# ForEK1.net
KiCad netlist of a schematic drawn in Altium Designer
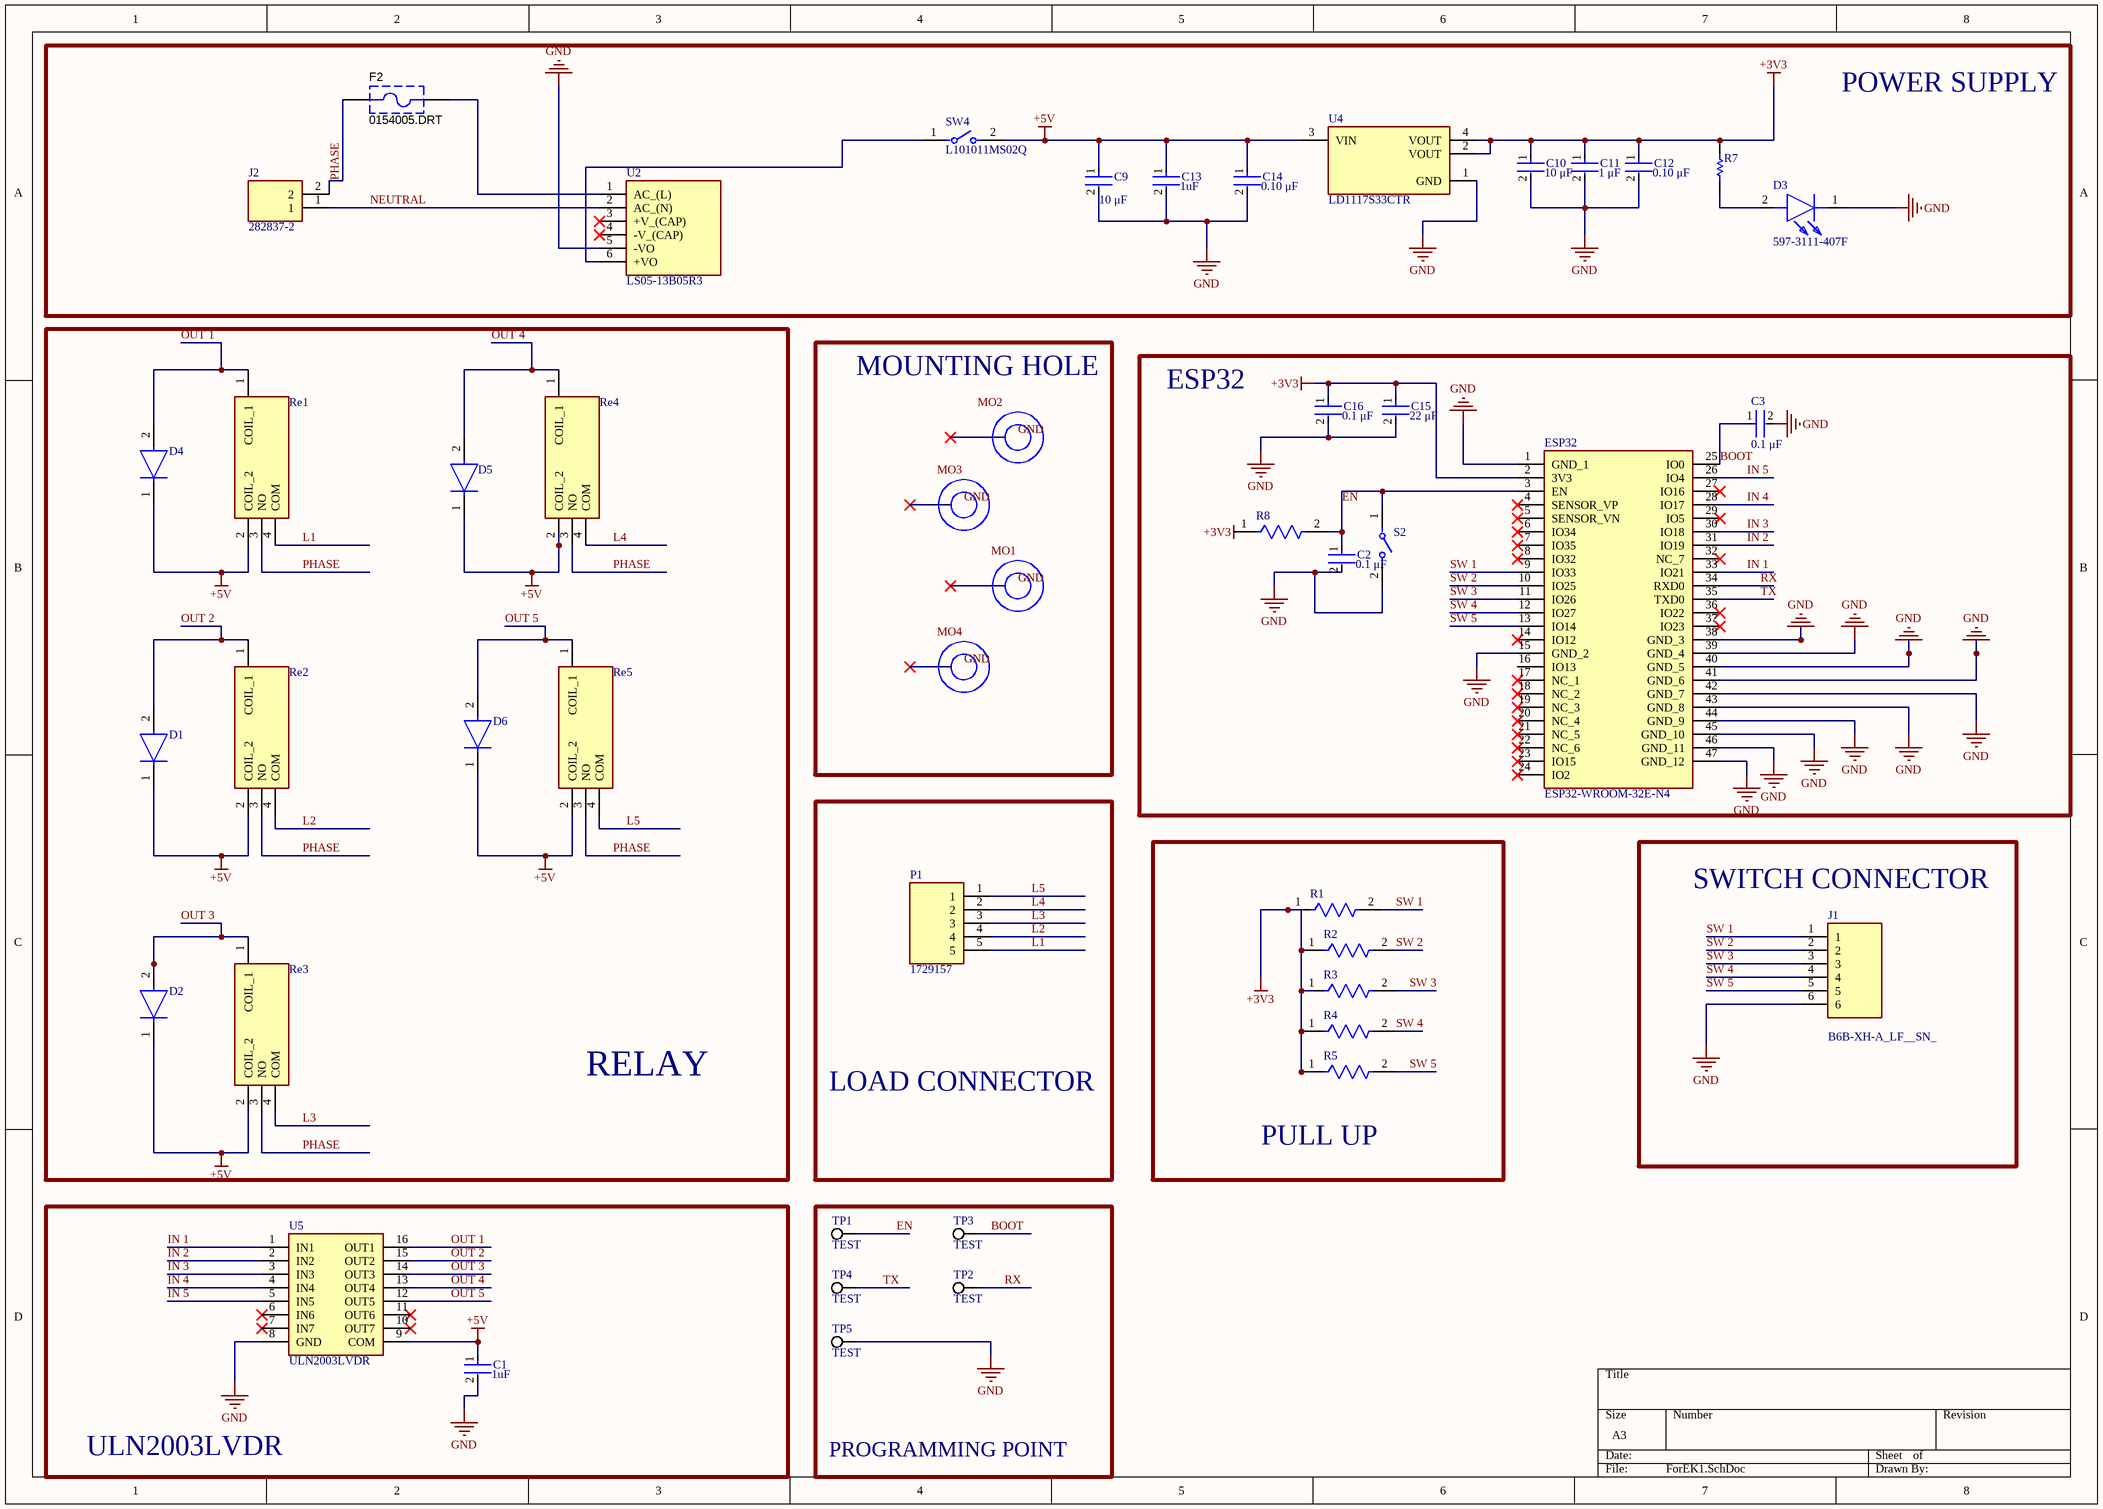
[diagram p0: ForEK1.SchDoc]

(export (version "E")
  (design (tool "Eeschema 10.0.6"))
  (components
    (comp (ref "C1")
      (value "C0402C104K8PACTU")
      (footprint "FP-C0402-BB-MFG")
      (description "CAP CER 0.1UF 10V X5R 0402")
      (fields
        (field (name "CAPACITANCE") "1uF")
        (field (name "MANUFACTURER") "Kemet")
        (field (name "TOLERANCE") "0.1")
      )
      (libsource (lib "Altium Content Vault") (part "b4654b650e69147ec39a6b967a45e02"))
    )
    (comp (ref "C2")
      (value "0.1 μF")
      (footprint "FP-C0402-BB-MFG")
      (description "CAP CER 0.1UF 10V X5R 0402")
      (fields (field (name "MANUFACTURER") "Kemet") (field (name "TOLERANCE") "0.1"))
      (libsource (lib "Altium Content Vault") (part "b4654b650e69147ec39a6b967a45e02"))
    )
    (comp (ref "C3")
      (value "0.1 μF")
      (footprint "FP-C0402-BB-MFG")
      (description "CAP CER 0.1UF 10V X5R 0402")
      (fields (field (name "MANUFACTURER") "Kemet") (field (name "TOLERANCE") "0.1"))
      (libsource (lib "Altium Content Vault") (part "b4654b650e69147ec39a6b967a45e02"))
    )
    (comp (ref "C9")
      (value "10 μF")
      (footprint "FP-C0402-BB-MFG")
      (description "CAP CER 0.1UF 10V X5R 0402")
      (fields (field (name "MANUFACTURER") "Kemet") (field (name "TOLERANCE") "0.1"))
      (libsource (lib "Altium Content Vault") (part "b4654b650e69147ec39a6b967a45e02"))
    )
    (comp (ref "C10")
      (value "10 μF")
      (footprint "FP-C0402-BB-MFG")
      (description "CAP CER 0.1UF 10V X5R 0402")
      (fields (field (name "MANUFACTURER") "Kemet") (field (name "TOLERANCE") "0.1"))
      (libsource (lib "Altium Content Vault") (part "b4654b650e69147ec39a6b967a45e02"))
    )
    (comp (ref "C11")
      (value "1 μF")
      (footprint "FP-C0402-BB-MFG")
      (description "CAP CER 0.1UF 10V X5R 0402")
      (fields (field (name "MANUFACTURER") "Kemet") (field (name "TOLERANCE") "0.1"))
      (libsource (lib "Altium Content Vault") (part "b4654b650e69147ec39a6b967a45e02"))
    )
    (comp (ref "C12")
      (value "C0402C104K8PACTU")
      (footprint "FP-C0402-BB-MFG")
      (description "CAP CER 0.1UF 10V X5R 0402")
      (fields
        (field (name "CAPACITANCE") "0.10 μF")
        (field (name "MANUFACTURER") "Kemet")
        (field (name "TOLERANCE") "0.1")
      )
      (libsource (lib "Altium Content Vault") (part "b4654b650e69147ec39a6b967a45e02"))
    )
    (comp (ref "C13")
      (value "C0402C104K8PACTU")
      (footprint "FP-C0402-BB-MFG")
      (description "CAP CER 0.1UF 10V X5R 0402")
      (fields
        (field (name "CAPACITANCE") "1uF")
        (field (name "MANUFACTURER") "Kemet")
        (field (name "TOLERANCE") "0.1")
      )
      (libsource (lib "Altium Content Vault") (part "b4654b650e69147ec39a6b967a45e02"))
    )
    (comp (ref "C14")
      (value "0.10 μF")
      (footprint "FP-C0402-BB-MFG")
      (description "CAP CER 0.1UF 10V X5R 0402")
      (fields (field (name "MANUFACTURER") "Kemet") (field (name "TOLERANCE") "0.1"))
      (libsource (lib "Altium Content Vault") (part "b4654b650e69147ec39a6b967a45e02"))
    )
    (comp (ref "C15")
      (value "22 μF")
      (footprint "FP-C0402-BB-MFG")
      (description "CAP CER 0.1UF 10V X5R 0402")
      (fields (field (name "MANUFACTURER") "Kemet") (field (name "TOLERANCE") "0.1"))
      (libsource (lib "Altium Content Vault") (part "b4654b650e69147ec39a6b967a45e02"))
    )
    (comp (ref "C16")
      (value "0.1 μF")
      (footprint "FP-C0402-BB-MFG")
      (description "CAP CER 0.1UF 10V X5R 0402")
      (fields (field (name "MANUFACTURER") "Kemet") (field (name "TOLERANCE") "0.1"))
      (libsource (lib "Altium Content Vault") (part "b4654b650e69147ec39a6b967a45e02"))
    )
    (comp (ref "D1")
      (value "1N4148")
      (footprint "FP-017AG-MFG")
      (description "DIODE GEN PURP 100V 200MA DO35")
      (fields (field (name "VOLTAGE") "100V"))
      (libsource (lib "Altium Content Vault") (part "d7152d700b627762746794eb795d46e"))
    )
    (comp (ref "D2")
      (value "1N4148")
      (footprint "FP-017AG-MFG")
      (description "DIODE GEN PURP 100V 200MA DO35")
      (fields (field (name "VOLTAGE") "100V"))
      (libsource (lib "Altium Content Vault") (part "d7152d700b627762746794eb795d46e"))
    )
    (comp (ref "D3")
      (value "597-3111-407F")
      (footprint "SamacSys:LEDC3015X150N")
      (description "LED")
      (fields (field (name "MOUSER PART NUMBER") "645-597-3111-407F"))
      (libsource (lib "*") (part "597-3111-407F"))
    )
    (comp (ref "D4")
      (value "1N4148")
      (footprint "FP-017AG-MFG")
      (description "DIODE GEN PURP 100V 200MA DO35")
      (fields (field (name "VOLTAGE") "100V"))
      (libsource (lib "Altium Content Vault") (part "d7152d700b627762746794eb795d46e"))
    )
    (comp (ref "D5")
      (value "1N4148")
      (footprint "FP-017AG-MFG")
      (description "DIODE GEN PURP 100V 200MA DO35")
      (fields (field (name "VOLTAGE") "100V"))
      (libsource (lib "Altium Content Vault") (part "d7152d700b627762746794eb795d46e"))
    )
    (comp (ref "D6")
      (value "1N4148")
      (footprint "FP-017AG-MFG")
      (description "DIODE GEN PURP 100V 200MA DO35")
      (fields (field (name "VOLTAGE") "100V"))
      (libsource (lib "Altium Content Vault") (part "d7152d700b627762746794eb795d46e"))
    )
    (comp (ref "ESP32")
      (value "ESP32-WROOM-32E-N4")
      (footprint "SamacSys:ESP32WROOM32EN4")
      (description "Integrated Circuit")
      (fields (field (name "MOUSER PART NUMBER") "356-ESP32WRM32E132PH"))
      (libsource (lib "*") (part "ESP32-WROOM-32E-N4"))
    )
    (comp (ref "F2")
      (value "0154005.DRT")
      (footprint "LFUS-154_V")
      (description "Fuse and Holder Combination, 125 V, 5 A, -55 to 125 degC, 2-Pin SMD, RoHS, Tape and Reel")
      (fields (field (name "MANUFACTURER") "Littelfuse"))
      (libsource (lib "Altium Content Vault") (part "FUSE_HOLDER-2"))
    )
    (comp (ref "J1")
      (value "B6B-XH-A_LF__SN_")
      (footprint "SamacSys:SHDR6W64P0X250_1X6_1740X575X700P")
      (description "Connector")
      (fields
        (field (name "MANUFACTURER_PART_NUMBER") "B6B-XH-A(LF)(SN)")
        (field (name "MOUSER PART NUMBER") "306-B6BXHALFSN")
      )
      (libsource (lib "*") (part "B6B-XH-A_LF__SN_"))
    )
    (comp (ref "J2")
      (value "282837-2")
      (footprint "SamacSys:2828372")
      (description "Connector")
      (fields (field (name "MOUSER PART NUMBER") "571-2828372"))
      (libsource (lib "*") (part "282837-2"))
    )
    (comp (ref "P1")
      (value "1729157")
      (footprint "SamacSys:1729157")
      (description "Connector")
      (fields (field (name "MOUSER PART NUMBER") "651-1729157"))
      (libsource (lib "*") (part "1729157"))
    )
    (comp (ref "R1")
      (value "CRCW040210K0JNED")
      (footprint "FP-CRCW0402-e3-IPC_B")
      (description "RES Thick Film, 10kΩ, 5%, 0.063W, 200ppm/°C, 0402")
      (fields (field (name "TOLERANCE") "5%"))
      (libsource (lib "Altium Content Vault") (part "1029c3af85768c4190bb7ad29bc67b5"))
    )
    (comp (ref "R2")
      (value "CRCW040210K0JNED")
      (footprint "FP-CRCW0402-e3-IPC_B")
      (description "RES Thick Film, 10kΩ, 5%, 0.063W, 200ppm/°C, 0402")
      (fields (field (name "TOLERANCE") "5%"))
      (libsource (lib "Altium Content Vault") (part "1029c3af85768c4190bb7ad29bc67b5"))
    )
    (comp (ref "R3")
      (value "CRCW040210K0JNED")
      (footprint "FP-CRCW0402-e3-IPC_B")
      (description "RES Thick Film, 10kΩ, 5%, 0.063W, 200ppm/°C, 0402")
      (fields (field (name "TOLERANCE") "5%"))
      (libsource (lib "Altium Content Vault") (part "1029c3af85768c4190bb7ad29bc67b5"))
    )
    (comp (ref "R4")
      (value "CRCW040210K0JNED")
      (footprint "FP-CRCW0402-e3-IPC_B")
      (description "RES Thick Film, 10kΩ, 5%, 0.063W, 200ppm/°C, 0402")
      (fields (field (name "TOLERANCE") "5%"))
      (libsource (lib "Altium Content Vault") (part "1029c3af85768c4190bb7ad29bc67b5"))
    )
    (comp (ref "R5")
      (value "CRCW040210K0JNED")
      (footprint "FP-CRCW0402-e3-IPC_B")
      (description "RES Thick Film, 10kΩ, 5%, 0.063W, 200ppm/°C, 0402")
      (fields (field (name "TOLERANCE") "5%"))
      (libsource (lib "Altium Content Vault") (part "1029c3af85768c4190bb7ad29bc67b5"))
    )
    (comp (ref "R7")
      (value "ERJ-3EKF3300V")
      (footprint "RESC1608X55X30LL15T15")
      (description "Chip Resistor, 330 Ohm, +/- 1%, 0.1 W, -55 to 155 degC, 0603 (1608 Metric), RoHS, Tape and Reel")
      (libsource (lib "Altium Content Vault") (part "RES-2"))
    )
    (comp (ref "R8")
      (value "CRCW040210K0JNED")
      (footprint "FP-CRCW0402-e3-IPC_B")
      (description "RES Thick Film, 10kΩ, 5%, 0.063W, 200ppm/°C, 0402")
      (fields (field (name "TOLERANCE") "5%"))
      (libsource (lib "Altium Content Vault") (part "1029c3af85768c4190bb7ad29bc67b5"))
    )
    (comp (ref "Re1")
      (value "HF46F-G_5-HS1T")
      (footprint "SamacSys:HF46FG5HS1T")
      (description "Relay or Contactor")
      (fields (field (name "MANUFACTURER_PART_NUMBER") "HF46F-G/5-HS1T"))
      (libsource (lib "*") (part "HF46F-G_5-HS1T"))
    )
    (comp (ref "Re2")
      (value "HF46F-G_5-HS1T")
      (footprint "SamacSys:HF46FG5HS1T")
      (description "Relay or Contactor")
      (fields (field (name "MANUFACTURER_PART_NUMBER") "HF46F-G/5-HS1T"))
      (libsource (lib "*") (part "HF46F-G_5-HS1T"))
    )
    (comp (ref "Re3")
      (value "HF46F-G_5-HS1T")
      (footprint "SamacSys:HF46FG5HS1T")
      (description "Relay or Contactor")
      (fields (field (name "MANUFACTURER_PART_NUMBER") "HF46F-G/5-HS1T"))
      (libsource (lib "*") (part "HF46F-G_5-HS1T"))
    )
    (comp (ref "Re4")
      (value "HF46F-G_5-HS1T")
      (footprint "SamacSys:HF46FG5HS1T")
      (description "Relay or Contactor")
      (fields (field (name "MANUFACTURER_PART_NUMBER") "HF46F-G/5-HS1T"))
      (libsource (lib "*") (part "HF46F-G_5-HS1T"))
    )
    (comp (ref "Re5")
      (value "HF46F-G_5-HS1T")
      (footprint "SamacSys:HF46FG5HS1T")
      (description "Relay or Contactor")
      (fields (field (name "MANUFACTURER_PART_NUMBER") "HF46F-G/5-HS1T"))
      (libsource (lib "*") (part "HF46F-G_5-HS1T"))
    )
    (comp (ref "S2")
      (value "L101011MS02Q")
      (footprint "FP-L101011MS02Q-MFG")
      (description "SWITCH SLIDE SPST 4A 125V")
      (libsource (lib "Altium Content Vault") (part "bb27bde45df87f1f469753f287ef5ae"))
    )
    (comp (ref "SW4")
      (value "L101011MS02Q")
      (footprint "FP-L101011MS02Q-MFG")
      (description "SWITCH SLIDE SPST 4A 125V")
      (libsource (lib "Altium Content Vault") (part "bb27bde45df87f1f469753f287ef5ae"))
    )
    (comp (ref "TP1")
      (value "TEST")
      (footprint "KSTN-5012_V")
      (description "Test Point, White, Through Hole, RoHS, Bulk")
      (fields (field (name "MANUFACTURER") "Keystone"))
      (libsource (lib "Altium Content Vault") (part "TESTPOINT_WHITE"))
    )
    (comp (ref "TP2")
      (value "TEST")
      (footprint "KSTN-5012_V")
      (description "Test Point, White, Through Hole, RoHS, Bulk")
      (fields (field (name "MANUFACTURER") "Keystone"))
      (libsource (lib "Altium Content Vault") (part "TESTPOINT_WHITE"))
    )
    (comp (ref "TP3")
      (value "TEST")
      (footprint "KSTN-5012_V")
      (description "Test Point, White, Through Hole, RoHS, Bulk")
      (fields (field (name "MANUFACTURER") "Keystone"))
      (libsource (lib "Altium Content Vault") (part "TESTPOINT_WHITE"))
    )
    (comp (ref "TP4")
      (value "TEST")
      (footprint "KSTN-5012_V")
      (description "Test Point, White, Through Hole, RoHS, Bulk")
      (fields (field (name "MANUFACTURER") "Keystone"))
      (libsource (lib "Altium Content Vault") (part "TESTPOINT_WHITE"))
    )
    (comp (ref "TP5")
      (value "TEST")
      (footprint "KSTN-5012_V")
      (description "Test Point, White, Through Hole, RoHS, Bulk")
      (fields (field (name "MANUFACTURER") "Keystone"))
      (libsource (lib "Altium Content Vault") (part "TESTPOINT_WHITE"))
    )
    (comp (ref "U2")
      (value "LS05-13B05R3")
      (footprint "SamacSys:LS0513B05R3")
      (description "Power Supply")
      (libsource (lib "*") (part "LS05-13B05R3"))
    )
    (comp (ref "U4")
      (value "LD1117S33CTR")
      (footprint "FP-SOT-223-0046067_14-MFG")
      (description "IC REG LINEAR 3.3V 800MA SOT223")
      (libsource (lib "Altium Content Vault") (part "7818869c5c16ceab15634627166a29d"))
    )
    (comp (ref "U5")
      (value "ULN2003LVDR")
      (footprint "SamacSys:SOIC127P600X175-16N")
      (description "Integrated Circuit")
      (fields (field (name "MOUSER PART NUMBER") "595-ULN2003LVDR"))
      (libsource (lib "*") (part "ULN2003LVDR"))
    )
  )
  (nets
    (net (code "1") (name "+3V3") (class "Default")
      (node (ref "C10") (pin "1") (pinfunction "1_1") (pintype "passive"))
      (node (ref "C11") (pin "1") (pinfunction "1_1") (pintype "passive"))
      (node (ref "C12") (pin "1") (pinfunction "1_1") (pintype "passive"))
      (node (ref "C15") (pin "1") (pinfunction "1_1") (pintype "passive"))
      (node (ref "C16") (pin "1") (pinfunction "1_1") (pintype "passive"))
      (node (ref "ESP32") (pin "2") (pinfunction "3V3_2") (pintype "passive"))
      (node (ref "R1") (pin "1") (pinfunction "1_1") (pintype "passive"))
      (node (ref "R2") (pin "1") (pinfunction "1_1") (pintype "passive"))
      (node (ref "R3") (pin "1") (pinfunction "1_1") (pintype "passive"))
      (node (ref "R4") (pin "1") (pinfunction "1_1") (pintype "passive"))
      (node (ref "R5") (pin "1") (pinfunction "1_1") (pintype "passive"))
      (node (ref "R7") (pin "2") (pinfunction "2_2") (pintype "passive"))
      (node (ref "U4") (pin "2") (pinfunction "VOUT_2") (pintype "power_in"))
      (node (ref "U4") (pin "4") (pinfunction "VOUT_4") (pintype "power_in"))
    )
    (net (code "2") (name "+5V") (class "Default")
      (node (ref "C1") (pin "1") (pinfunction "1_1") (pintype "passive"))
      (node (ref "C13") (pin "1") (pinfunction "1_1") (pintype "passive"))
      (node (ref "C14") (pin "1") (pinfunction "1_1") (pintype "passive"))
      (node (ref "C9") (pin "1") (pinfunction "1_1") (pintype "passive"))
      (node (ref "D1") (pin "1") (pinfunction "C_1") (pintype "passive"))
      (node (ref "D2") (pin "1") (pinfunction "C_1") (pintype "passive"))
      (node (ref "D4") (pin "1") (pinfunction "C_1") (pintype "passive"))
      (node (ref "D5") (pin "1") (pinfunction "C_1") (pintype "passive"))
      (node (ref "D6") (pin "1") (pinfunction "C_1") (pintype "passive"))
      (node (ref "Re1") (pin "2") (pinfunction "COIL_2_2") (pintype "passive"))
      (node (ref "Re2") (pin "2") (pinfunction "COIL_2_2") (pintype "passive"))
      (node (ref "Re3") (pin "2") (pinfunction "COIL_2_2") (pintype "passive"))
      (node (ref "Re4") (pin "2") (pinfunction "COIL_2_2") (pintype "passive"))
      (node (ref "Re5") (pin "2") (pinfunction "COIL_2_2") (pintype "passive"))
      (node (ref "SW4") (pin "2") (pinfunction "2_2") (pintype "passive"))
      (node (ref "U4") (pin "3") (pinfunction "VIN_3") (pintype "power_in"))
      (node (ref "U5") (pin "9") (pinfunction "COM_9") (pintype "passive"))
    )
    (net (code "3") (name "/BOOT") (class "Default")
      (node (ref "C3") (pin "1") (pinfunction "1_1") (pintype "passive"))
      (node (ref "ESP32") (pin "25") (pinfunction "IO0_25") (pintype "passive"))
      (node (ref "TP3") (pin "1") (pinfunction "1_1") (pintype "passive"))
    )
    (net (code "4") (name "/EN") (class "Default")
      (node (ref "C2") (pin "1") (pinfunction "1_1") (pintype "passive"))
      (node (ref "ESP32") (pin "3") (pinfunction "EN_3") (pintype "passive"))
      (node (ref "R8") (pin "2") (pinfunction "2_2") (pintype "passive"))
      (node (ref "S2") (pin "1") (pinfunction "1_1") (pintype "passive"))
      (node (ref "TP1") (pin "1") (pinfunction "1_1") (pintype "passive"))
    )
    (net (code "5") (name "/IN 1") (class "Default")
      (node (ref "ESP32") (pin "33") (pinfunction "IO21_33") (pintype "passive"))
      (node (ref "U5") (pin "1") (pinfunction "IN1_1") (pintype "passive"))
    )
    (net (code "6") (name "/IN 2") (class "Default")
      (node (ref "ESP32") (pin "31") (pinfunction "IO19_31") (pintype "passive"))
      (node (ref "U5") (pin "2") (pinfunction "IN2_2") (pintype "passive"))
    )
    (net (code "7") (name "/IN 3") (class "Default")
      (node (ref "ESP32") (pin "30") (pinfunction "IO18_30") (pintype "passive"))
      (node (ref "U5") (pin "3") (pinfunction "IN3_3") (pintype "passive"))
    )
    (net (code "8") (name "/IN 4") (class "Default")
      (node (ref "ESP32") (pin "28") (pinfunction "IO17_28") (pintype "passive"))
      (node (ref "U5") (pin "4") (pinfunction "IN4_4") (pintype "passive"))
    )
    (net (code "9") (name "/IN 5") (class "Default")
      (node (ref "ESP32") (pin "26") (pinfunction "IO4_26") (pintype "passive"))
      (node (ref "U5") (pin "5") (pinfunction "IN5_5") (pintype "passive"))
    )
    (net (code "10") (name "/L1") (class "Default")
      (node (ref "P1") (pin "5") (pinfunction "5_5") (pintype "passive"))
      (node (ref "Re1") (pin "4") (pinfunction "COM_4") (pintype "passive"))
    )
    (net (code "11") (name "/L2") (class "Default")
      (node (ref "P1") (pin "4") (pinfunction "4_4") (pintype "passive"))
      (node (ref "Re2") (pin "4") (pinfunction "COM_4") (pintype "passive"))
    )
    (net (code "12") (name "/L3") (class "Default")
      (node (ref "P1") (pin "3") (pinfunction "3_3") (pintype "passive"))
      (node (ref "Re3") (pin "4") (pinfunction "COM_4") (pintype "passive"))
    )
    (net (code "13") (name "/L4") (class "Default")
      (node (ref "P1") (pin "2") (pinfunction "2_2") (pintype "passive"))
      (node (ref "Re4") (pin "4") (pinfunction "COM_4") (pintype "passive"))
    )
    (net (code "14") (name "/L5") (class "Default")
      (node (ref "P1") (pin "1") (pinfunction "1_1") (pintype "passive"))
      (node (ref "Re5") (pin "4") (pinfunction "COM_4") (pintype "passive"))
    )
    (net (code "19") (name "/NEUTRAL") (class "Default")
      (node (ref "J2") (pin "1") (pinfunction "1_1") (pintype "passive"))
      (node (ref "U2") (pin "2") (pinfunction "AC_(N)_2") (pintype "passive"))
    )
    (net (code "20") (name "/OUT 1") (class "Default")
      (node (ref "D4") (pin "2") (pinfunction "A_2") (pintype "passive"))
      (node (ref "Re1") (pin "1") (pinfunction "COIL_1_1") (pintype "passive"))
      (node (ref "U5") (pin "16") (pinfunction "OUT1_16") (pintype "passive"))
    )
    (net (code "21") (name "/OUT 2") (class "Default")
      (node (ref "D1") (pin "2") (pinfunction "A_2") (pintype "passive"))
      (node (ref "Re2") (pin "1") (pinfunction "COIL_1_1") (pintype "passive"))
      (node (ref "U5") (pin "15") (pinfunction "OUT2_15") (pintype "passive"))
    )
    (net (code "22") (name "/OUT 3") (class "Default")
      (node (ref "D2") (pin "2") (pinfunction "A_2") (pintype "passive"))
      (node (ref "Re3") (pin "1") (pinfunction "COIL_1_1") (pintype "passive"))
      (node (ref "U5") (pin "14") (pinfunction "OUT3_14") (pintype "passive"))
    )
    (net (code "23") (name "/OUT 4") (class "Default")
      (node (ref "D5") (pin "2") (pinfunction "A_2") (pintype "passive"))
      (node (ref "Re4") (pin "1") (pinfunction "COIL_1_1") (pintype "passive"))
      (node (ref "U5") (pin "13") (pinfunction "OUT4_13") (pintype "passive"))
    )
    (net (code "24") (name "/OUT 5") (class "Default")
      (node (ref "D6") (pin "2") (pinfunction "A_2") (pintype "passive"))
      (node (ref "Re5") (pin "1") (pinfunction "COIL_1_1") (pintype "passive"))
      (node (ref "U5") (pin "12") (pinfunction "OUT5_12") (pintype "passive"))
    )
    (net (code "25") (name "/PHASE") (class "Default")
      (node (ref "F2") (pin "1") (pinfunction "1_1") (pintype "passive"))
      (node (ref "J2") (pin "2") (pinfunction "2_2") (pintype "passive"))
      (node (ref "Re1") (pin "3") (pinfunction "NO_3") (pintype "passive"))
      (node (ref "Re2") (pin "3") (pinfunction "NO_3") (pintype "passive"))
      (node (ref "Re3") (pin "3") (pinfunction "NO_3") (pintype "passive"))
      (node (ref "Re4") (pin "3") (pinfunction "NO_3") (pintype "passive"))
      (node (ref "Re5") (pin "3") (pinfunction "NO_3") (pintype "passive"))
    )
    (net (code "26") (name "/RX") (class "Default")
      (node (ref "ESP32") (pin "34") (pinfunction "RXD0_34") (pintype "passive"))
      (node (ref "TP2") (pin "1") (pinfunction "1_1") (pintype "passive"))
    )
    (net (code "27") (name "/SW 1") (class "Default")
      (node (ref "ESP32") (pin "9") (pinfunction "IO33_9") (pintype "passive"))
      (node (ref "J1") (pin "1") (pinfunction "1_1") (pintype "passive"))
      (node (ref "R1") (pin "2") (pinfunction "2_2") (pintype "passive"))
    )
    (net (code "28") (name "/SW 2") (class "Default")
      (node (ref "ESP32") (pin "10") (pinfunction "IO25_10") (pintype "passive"))
      (node (ref "J1") (pin "2") (pinfunction "2_2") (pintype "passive"))
      (node (ref "R2") (pin "2") (pinfunction "2_2") (pintype "passive"))
    )
    (net (code "29") (name "/SW 3") (class "Default")
      (node (ref "ESP32") (pin "11") (pinfunction "IO26_11") (pintype "passive"))
      (node (ref "J1") (pin "3") (pinfunction "3_3") (pintype "passive"))
      (node (ref "R3") (pin "2") (pinfunction "2_2") (pintype "passive"))
    )
    (net (code "30") (name "/SW 4") (class "Default")
      (node (ref "ESP32") (pin "12") (pinfunction "IO27_12") (pintype "passive"))
      (node (ref "J1") (pin "4") (pinfunction "4_4") (pintype "passive"))
      (node (ref "R4") (pin "2") (pinfunction "2_2") (pintype "passive"))
    )
    (net (code "31") (name "/SW 5") (class "Default")
      (node (ref "ESP32") (pin "13") (pinfunction "IO14_13") (pintype "passive"))
      (node (ref "J1") (pin "5") (pinfunction "5_5") (pintype "passive"))
      (node (ref "R5") (pin "2") (pinfunction "2_2") (pintype "passive"))
    )
    (net (code "32") (name "/TX") (class "Default")
      (node (ref "ESP32") (pin "35") (pinfunction "TXD0_35") (pintype "passive"))
      (node (ref "TP4") (pin "1") (pinfunction "1_1") (pintype "passive"))
    )
    (net (code "33") (name "GND") (class "Default")
      (node (ref "C1") (pin "2") (pinfunction "2_2") (pintype "passive"))
      (node (ref "C10") (pin "2") (pinfunction "2_2") (pintype "passive"))
      (node (ref "C11") (pin "2") (pinfunction "2_2") (pintype "passive"))
      (node (ref "C12") (pin "2") (pinfunction "2_2") (pintype "passive"))
      (node (ref "C13") (pin "2") (pinfunction "2_2") (pintype "passive"))
      (node (ref "C14") (pin "2") (pinfunction "2_2") (pintype "passive"))
      (node (ref "C15") (pin "2") (pinfunction "2_2") (pintype "passive"))
      (node (ref "C16") (pin "2") (pinfunction "2_2") (pintype "passive"))
      (node (ref "C2") (pin "2") (pinfunction "2_2") (pintype "passive"))
      (node (ref "C3") (pin "2") (pinfunction "2_2") (pintype "passive"))
      (node (ref "C9") (pin "2") (pinfunction "2_2") (pintype "passive"))
      (node (ref "D3") (pin "1") (pinfunction "K_1") (pintype "passive"))
      (node (ref "ESP32") (pin "1") (pinfunction "GND_1_1") (pintype "passive"))
      (node (ref "ESP32") (pin "15") (pinfunction "GND_2_15") (pintype "passive"))
      (node (ref "ESP32") (pin "38") (pinfunction "GND_3_38") (pintype "passive"))
      (node (ref "ESP32") (pin "39") (pinfunction "GND_4_39") (pintype "passive"))
      (node (ref "ESP32") (pin "40") (pinfunction "GND_5_40") (pintype "passive"))
      (node (ref "ESP32") (pin "41") (pinfunction "GND_6_41") (pintype "passive"))
      (node (ref "ESP32") (pin "42") (pinfunction "GND_7_42") (pintype "passive"))
      (node (ref "ESP32") (pin "43") (pinfunction "GND_8_43") (pintype "passive"))
      (node (ref "ESP32") (pin "44") (pinfunction "GND_9_44") (pintype "passive"))
      (node (ref "ESP32") (pin "45") (pinfunction "GND_10_45") (pintype "passive"))
      (node (ref "ESP32") (pin "46") (pinfunction "GND_11_46") (pintype "passive"))
      (node (ref "ESP32") (pin "47") (pinfunction "GND_12_47") (pintype "passive"))
      (node (ref "J1") (pin "6") (pinfunction "6_6") (pintype "passive"))
      (node (ref "S2") (pin "2") (pinfunction "2_2") (pintype "passive"))
      (node (ref "TP5") (pin "1") (pinfunction "1_1") (pintype "passive"))
      (node (ref "U2") (pin "5") (pinfunction "-VO_5") (pintype "passive"))
      (node (ref "U4") (pin "1") (pinfunction "GND_1") (pintype "power_in"))
      (node (ref "U5") (pin "8") (pinfunction "GND_8") (pintype "passive"))
    )
    (net (code "34") (name "Net-(D3-A)") (class "Default")
      (node (ref "D3") (pin "2") (pinfunction "A_2") (pintype "passive"))
      (node (ref "R7") (pin "1") (pinfunction "1_1") (pintype "passive"))
    )
    (net (code "35") (name "Net-(U2-+VO)") (class "Default")
      (node (ref "SW4") (pin "1") (pinfunction "1_1") (pintype "passive"))
      (node (ref "U2") (pin "6") (pinfunction "+VO_6") (pintype "passive"))
    )
    (net (code "36") (name "Net-(U2-AC_(L))") (class "Default")
      (node (ref "F2") (pin "2") (pinfunction "2_2") (pintype "passive"))
      (node (ref "U2") (pin "1") (pinfunction "AC_(L)_1") (pintype "passive"))
    )
    (net (code "37") (name "unconnected-(ESP32-IO2-Pad24)") (class "Default")
      (node (ref "ESP32") (pin "24") (pinfunction "IO2_24") (pintype "passive+no_connect"))
    )
    (net (code "38") (name "unconnected-(ESP32-IO5-Pad29)") (class "Default")
      (node (ref "ESP32") (pin "29") (pinfunction "IO5_29") (pintype "passive+no_connect"))
    )
    (net (code "39") (name "unconnected-(ESP32-IO12-Pad14)") (class "Default")
      (node (ref "ESP32") (pin "14") (pinfunction "IO12_14") (pintype "passive+no_connect"))
    )
    (net (code "40") (name "unconnected-(ESP32-IO13-Pad16)") (class "Default")
      (node (ref "ESP32") (pin "16") (pinfunction "IO13_16") (pintype "passive"))
    )
    (net (code "41") (name "unconnected-(ESP32-IO15-Pad23)") (class "Default")
      (node (ref "ESP32") (pin "23") (pinfunction "IO15_23") (pintype "passive+no_connect"))
    )
    (net (code "42") (name "unconnected-(ESP32-IO16-Pad27)") (class "Default")
      (node (ref "ESP32") (pin "27") (pinfunction "IO16_27") (pintype "passive+no_connect"))
    )
    (net (code "43") (name "unconnected-(ESP32-IO22-Pad36)") (class "Default")
      (node (ref "ESP32") (pin "36") (pinfunction "IO22_36") (pintype "passive+no_connect"))
    )
    (net (code "44") (name "unconnected-(ESP32-IO23-Pad37)") (class "Default")
      (node (ref "ESP32") (pin "37") (pinfunction "IO23_37") (pintype "passive+no_connect"))
    )
    (net (code "45") (name "unconnected-(ESP32-IO32-Pad8)") (class "Default")
      (node (ref "ESP32") (pin "8") (pinfunction "IO32_8") (pintype "passive+no_connect"))
    )
    (net (code "46") (name "unconnected-(ESP32-IO34-Pad6)") (class "Default")
      (node (ref "ESP32") (pin "6") (pinfunction "IO34_6") (pintype "passive+no_connect"))
    )
    (net (code "47") (name "unconnected-(ESP32-IO35-Pad7)") (class "Default")
      (node (ref "ESP32") (pin "7") (pinfunction "IO35_7") (pintype "passive+no_connect"))
    )
    (net (code "48") (name "unconnected-(ESP32-NC_1-Pad17)") (class "Default")
      (node (ref "ESP32") (pin "17") (pinfunction "NC_1_17") (pintype "passive+no_connect"))
    )
    (net (code "49") (name "unconnected-(ESP32-NC_2-Pad18)") (class "Default")
      (node (ref "ESP32") (pin "18") (pinfunction "NC_2_18") (pintype "passive+no_connect"))
    )
    (net (code "50") (name "unconnected-(ESP32-NC_3-Pad19)") (class "Default")
      (node (ref "ESP32") (pin "19") (pinfunction "NC_3_19") (pintype "passive+no_connect"))
    )
    (net (code "51") (name "unconnected-(ESP32-NC_4-Pad20)") (class "Default")
      (node (ref "ESP32") (pin "20") (pinfunction "NC_4_20") (pintype "passive+no_connect"))
    )
    (net (code "52") (name "unconnected-(ESP32-NC_5-Pad21)") (class "Default")
      (node (ref "ESP32") (pin "21") (pinfunction "NC_5_21") (pintype "passive+no_connect"))
    )
    (net (code "53") (name "unconnected-(ESP32-NC_6-Pad22)") (class "Default")
      (node (ref "ESP32") (pin "22") (pinfunction "NC_6_22") (pintype "passive+no_connect"))
    )
    (net (code "54") (name "unconnected-(ESP32-NC_7-Pad32)") (class "Default")
      (node (ref "ESP32") (pin "32") (pinfunction "NC_7_32") (pintype "passive+no_connect"))
    )
    (net (code "55") (name "unconnected-(ESP32-SENSOR_VN-Pad5)") (class "Default")
      (node (ref "ESP32") (pin "5") (pinfunction "SENSOR_VN_5") (pintype "passive+no_connect"))
    )
    (net (code "56") (name "unconnected-(ESP32-SENSOR_VP-Pad4)") (class "Default")
      (node (ref "ESP32") (pin "4") (pinfunction "SENSOR_VP_4") (pintype "passive+no_connect"))
    )
    (net (code "57") (name "unconnected-(R8-Pad1)") (class "Default")
      (node (ref "R8") (pin "1") (pinfunction "1_1") (pintype "passive"))
    )
    (net (code "58") (name "unconnected-(U2-+V_(CAP)-Pad3)") (class "Default")
      (node (ref "U2") (pin "3") (pinfunction "+V_(CAP)_3") (pintype "passive+no_connect"))
    )
    (net (code "59") (name "unconnected-(U2--V_(CAP)-Pad4)") (class "Default")
      (node (ref "U2") (pin "4") (pinfunction "-V_(CAP)_4") (pintype "passive+no_connect"))
    )
    (net (code "60") (name "unconnected-(U5-IN6-Pad6)") (class "Default")
      (node (ref "U5") (pin "6") (pinfunction "IN6_6") (pintype "passive+no_connect"))
    )
    (net (code "61") (name "unconnected-(U5-IN7-Pad7)") (class "Default")
      (node (ref "U5") (pin "7") (pinfunction "IN7_7") (pintype "passive+no_connect"))
    )
    (net (code "62") (name "unconnected-(U5-OUT6-Pad11)") (class "Default")
      (node (ref "U5") (pin "11") (pinfunction "OUT6_11") (pintype "passive+no_connect"))
    )
    (net (code "63") (name "unconnected-(U5-OUT7-Pad10)") (class "Default")
      (node (ref "U5") (pin "10") (pinfunction "OUT7_10") (pintype "passive+no_connect"))
    )
  )
)
